# Current_Sense_Board.net
KiCad netlist of a schematic drawn in EAGLE
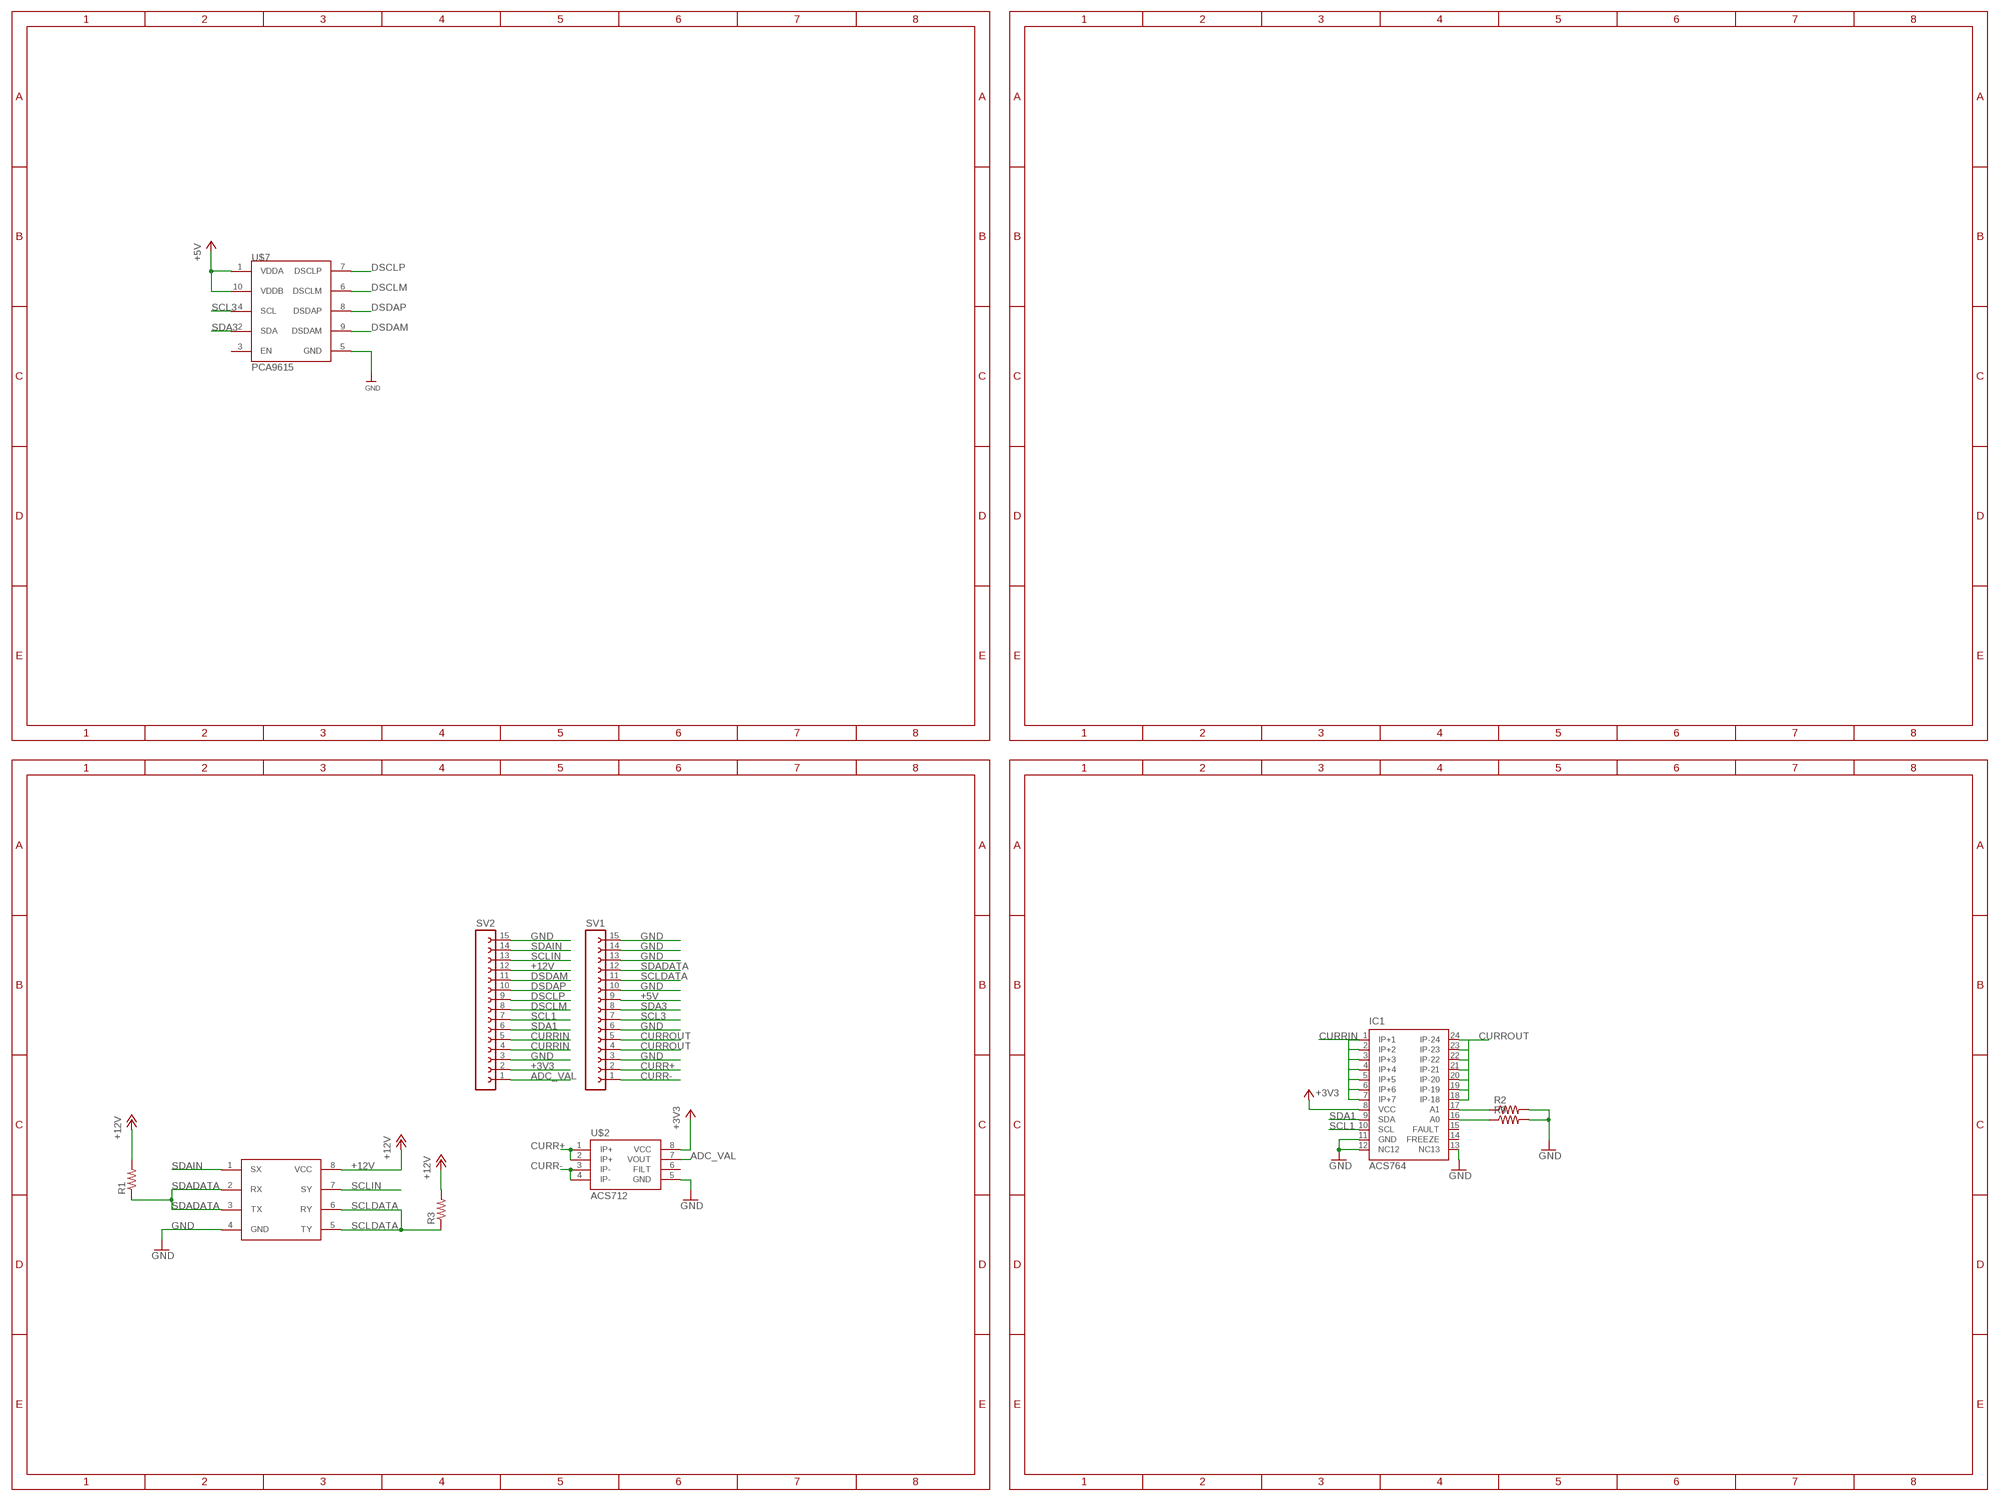
[diagram p0: schematic, sheet 1]

(export (version "E")
  (design (tool "Eeschema 10.0.6"))
  (components
    (comp (ref "IC1")
      (value "ACS764")
      (footprint "eagle-import:SSOP24")
      (libsource (lib "eagle-import") (part "ACS764"))
    )
    (comp (ref "R1")
      (value "RESISTOR0603")
      (footprint "eagle-import:0603-RES")
      (libsource (lib "eagle-import") (part "RESISTOR0603"))
    )
    (comp (ref "R2")
      (value "RESISTOR0603")
      (footprint "eagle-import:0603-RES")
      (libsource (lib "eagle-import") (part "RESISTOR0603"))
    )
    (comp (ref "R3")
      (value "RESISTOR0603")
      (footprint "eagle-import:0603-RES")
      (libsource (lib "eagle-import") (part "RESISTOR0603"))
    )
    (comp (ref "R9")
      (value "RESISTOR0603")
      (footprint "eagle-import:0603-RES")
      (libsource (lib "eagle-import") (part "RESISTOR0603"))
    )
    (comp (ref "SV1")
      (value "FE15-1")
      (footprint "eagle-import:FE15")
      (libsource (lib "eagle-import") (part "FE15-1"))
    )
    (comp (ref "SV2")
      (value "FE15-1")
      (footprint "eagle-import:FE15")
      (libsource (lib "eagle-import") (part "FE15-1"))
    )
    (comp (ref "U$1")
      (value "PCA9000")
      (footprint "eagle-import:TSSOP8")
      (libsource (lib "eagle-import") (part "PCA9000"))
    )
    (comp (ref "U$2")
      (value "ACS712")
      (footprint "eagle-import:SO08")
      (libsource (lib "eagle-import") (part "ACS712"))
    )
    (comp (ref "U$7")
      (value "PCA9615")
      (footprint "eagle-import:MSOP_10")
      (libsource (lib "eagle-import") (part "PCA9615"))
    )
  )
  (nets
    (net (code "1") (name "+3V3") (class "Default")
      (node (ref "IC1") (pin "8") (pinfunction "VCC_8") (pintype "bidirectional"))
      (node (ref "SV2") (pin "2") (pinfunction "2_2") (pintype "passive"))
      (node (ref "U$2") (pin "8") (pinfunction "VCC_8") (pintype "bidirectional"))
    )
    (net (code "2") (name "+5V") (class "Default")
      (node (ref "SV1") (pin "9") (pinfunction "9_9") (pintype "passive"))
      (node (ref "U$7") (pin "1") (pinfunction "VDDA_1") (pintype "bidirectional"))
      (node (ref "U$7") (pin "10") (pinfunction "VDDB_10") (pintype "bidirectional"))
    )
    (net (code "3") (name "+12V") (class "Default")
      (node (ref "R1") (pin "2") (pinfunction "2_2") (pintype "passive"))
      (node (ref "R3") (pin "2") (pinfunction "2_2") (pintype "passive"))
      (node (ref "SV2") (pin "12") (pinfunction "12_12") (pintype "passive"))
      (node (ref "U$1") (pin "8") (pinfunction "VCC_8") (pintype "bidirectional"))
    )
    (net (code "4") (name "ADC_VAL") (class "Default")
      (node (ref "SV2") (pin "1") (pinfunction "1_1") (pintype "passive"))
      (node (ref "U$2") (pin "7") (pinfunction "VOUT_7") (pintype "bidirectional"))
    )
    (net (code "5") (name "CURR+") (class "Default")
      (node (ref "SV1") (pin "2") (pinfunction "2_2") (pintype "passive"))
      (node (ref "U$2") (pin "1") (pinfunction "IP+_1") (pintype "bidirectional"))
      (node (ref "U$2") (pin "2") (pinfunction "IP+_2") (pintype "bidirectional"))
    )
    (net (code "6") (name "CURR-") (class "Default")
      (node (ref "SV1") (pin "1") (pinfunction "1_1") (pintype "passive"))
      (node (ref "U$2") (pin "3") (pinfunction "IP-_3") (pintype "bidirectional"))
      (node (ref "U$2") (pin "4") (pinfunction "IP-_4") (pintype "bidirectional"))
    )
    (net (code "7") (name "CURRIN") (class "Default")
      (node (ref "IC1") (pin "1") (pinfunction "IP+1_1") (pintype "bidirectional"))
      (node (ref "IC1") (pin "2") (pinfunction "IP+2_2") (pintype "bidirectional"))
      (node (ref "IC1") (pin "3") (pinfunction "IP+3_3") (pintype "bidirectional"))
      (node (ref "IC1") (pin "4") (pinfunction "IP+4_4") (pintype "bidirectional"))
      (node (ref "IC1") (pin "5") (pinfunction "IP+5_5") (pintype "bidirectional"))
      (node (ref "IC1") (pin "6") (pinfunction "IP+6_6") (pintype "bidirectional"))
      (node (ref "IC1") (pin "7") (pinfunction "IP+7_7") (pintype "bidirectional"))
      (node (ref "SV2") (pin "4") (pinfunction "4_4") (pintype "passive"))
      (node (ref "SV2") (pin "5") (pinfunction "5_5") (pintype "passive"))
    )
    (net (code "8") (name "CURROUT") (class "Default")
      (node (ref "IC1") (pin "18") (pinfunction "IP-18_18") (pintype "bidirectional"))
      (node (ref "IC1") (pin "19") (pinfunction "IP-19_19") (pintype "bidirectional"))
      (node (ref "IC1") (pin "20") (pinfunction "IP-20_20") (pintype "bidirectional"))
      (node (ref "IC1") (pin "21") (pinfunction "IP-21_21") (pintype "bidirectional"))
      (node (ref "IC1") (pin "22") (pinfunction "IP-22_22") (pintype "bidirectional"))
      (node (ref "IC1") (pin "23") (pinfunction "IP-23_23") (pintype "bidirectional"))
      (node (ref "IC1") (pin "24") (pinfunction "IP-24_24") (pintype "bidirectional"))
      (node (ref "SV1") (pin "4") (pinfunction "4_4") (pintype "passive"))
      (node (ref "SV1") (pin "5") (pinfunction "5_5") (pintype "passive"))
    )
    (net (code "9") (name "DSCLM") (class "Default")
      (node (ref "SV2") (pin "8") (pinfunction "8_8") (pintype "passive"))
      (node (ref "U$7") (pin "6") (pinfunction "DSCLM_6") (pintype "bidirectional"))
    )
    (net (code "10") (name "DSCLP") (class "Default")
      (node (ref "SV2") (pin "9") (pinfunction "9_9") (pintype "passive"))
      (node (ref "U$7") (pin "7") (pinfunction "DSCLP_7") (pintype "bidirectional"))
    )
    (net (code "11") (name "DSDAM") (class "Default")
      (node (ref "SV2") (pin "11") (pinfunction "11_11") (pintype "passive"))
      (node (ref "U$7") (pin "9") (pinfunction "DSDAM_9") (pintype "bidirectional"))
    )
    (net (code "12") (name "DSDAP") (class "Default")
      (node (ref "SV2") (pin "10") (pinfunction "10_10") (pintype "passive"))
      (node (ref "U$7") (pin "8") (pinfunction "DSDAP_8") (pintype "bidirectional"))
    )
    (net (code "13") (name "GND") (class "Default")
      (node (ref "IC1") (pin "11") (pinfunction "GND_11") (pintype "bidirectional"))
      (node (ref "IC1") (pin "12") (pinfunction "NC12_12") (pintype "bidirectional"))
      (node (ref "IC1") (pin "13") (pinfunction "NC13_13") (pintype "bidirectional"))
      (node (ref "R2") (pin "2") (pinfunction "2_2") (pintype "passive"))
      (node (ref "R9") (pin "2") (pinfunction "2_2") (pintype "passive"))
      (node (ref "SV1") (pin "10") (pinfunction "10_10") (pintype "passive"))
      (node (ref "SV1") (pin "13") (pinfunction "13_13") (pintype "passive"))
      (node (ref "SV1") (pin "14") (pinfunction "14_14") (pintype "passive"))
      (node (ref "SV1") (pin "15") (pinfunction "15_15") (pintype "passive"))
      (node (ref "SV1") (pin "3") (pinfunction "3_3") (pintype "passive"))
      (node (ref "SV1") (pin "6") (pinfunction "6_6") (pintype "passive"))
      (node (ref "SV2") (pin "15") (pinfunction "15_15") (pintype "passive"))
      (node (ref "SV2") (pin "3") (pinfunction "3_3") (pintype "passive"))
      (node (ref "U$1") (pin "4") (pinfunction "GND_4") (pintype "bidirectional"))
      (node (ref "U$2") (pin "5") (pinfunction "GND_5") (pintype "bidirectional"))
      (node (ref "U$7") (pin "5") (pinfunction "GND_5") (pintype "bidirectional"))
    )
    (net (code "14") (name "Net-(IC1-A0)") (class "Default")
      (node (ref "IC1") (pin "16") (pinfunction "A0_16") (pintype "bidirectional"))
      (node (ref "R9") (pin "1") (pinfunction "1_1") (pintype "passive"))
    )
    (net (code "15") (name "Net-(IC1-A1)") (class "Default")
      (node (ref "IC1") (pin "17") (pinfunction "A1_17") (pintype "bidirectional"))
      (node (ref "R2") (pin "1") (pinfunction "1_1") (pintype "passive"))
    )
    (net (code "16") (name "SCL1") (class "Default")
      (node (ref "IC1") (pin "10") (pinfunction "SCL_10") (pintype "bidirectional"))
      (node (ref "SV2") (pin "7") (pinfunction "7_7") (pintype "passive"))
    )
    (net (code "17") (name "SCL3") (class "Default")
      (node (ref "SV1") (pin "7") (pinfunction "7_7") (pintype "passive"))
      (node (ref "U$7") (pin "4") (pinfunction "SCL_4") (pintype "bidirectional"))
    )
    (net (code "18") (name "SCLDATA") (class "Default")
      (node (ref "R3") (pin "1") (pinfunction "1_1") (pintype "passive"))
      (node (ref "SV1") (pin "11") (pinfunction "11_11") (pintype "passive"))
      (node (ref "U$1") (pin "5") (pinfunction "TY_5") (pintype "bidirectional"))
      (node (ref "U$1") (pin "6") (pinfunction "RY_6") (pintype "bidirectional"))
    )
    (net (code "19") (name "SCLIN") (class "Default")
      (node (ref "SV2") (pin "13") (pinfunction "13_13") (pintype "passive"))
      (node (ref "U$1") (pin "7") (pinfunction "SY_7") (pintype "bidirectional"))
    )
    (net (code "20") (name "SDA1") (class "Default")
      (node (ref "IC1") (pin "9") (pinfunction "SDA_9") (pintype "bidirectional"))
      (node (ref "SV2") (pin "6") (pinfunction "6_6") (pintype "passive"))
    )
    (net (code "21") (name "SDA3") (class "Default")
      (node (ref "SV1") (pin "8") (pinfunction "8_8") (pintype "passive"))
      (node (ref "U$7") (pin "2") (pinfunction "SDA_2") (pintype "bidirectional"))
    )
    (net (code "22") (name "SDADATA") (class "Default")
      (node (ref "R1") (pin "1") (pinfunction "1_1") (pintype "passive"))
      (node (ref "SV1") (pin "12") (pinfunction "12_12") (pintype "passive"))
      (node (ref "U$1") (pin "2") (pinfunction "RX_2") (pintype "bidirectional"))
      (node (ref "U$1") (pin "3") (pinfunction "TX_3") (pintype "bidirectional"))
    )
    (net (code "23") (name "SDAIN") (class "Default")
      (node (ref "SV2") (pin "14") (pinfunction "14_14") (pintype "passive"))
      (node (ref "U$1") (pin "1") (pinfunction "SX_1") (pintype "bidirectional"))
    )
    (net (code "24") (name "unconnected-(IC1-FAULT-Pad15)") (class "Default")
      (node (ref "IC1") (pin "15") (pinfunction "FAULT_15") (pintype "bidirectional"))
    )
    (net (code "25") (name "unconnected-(IC1-FREEZE-Pad14)") (class "Default")
      (node (ref "IC1") (pin "14") (pinfunction "FREEZE_14") (pintype "bidirectional"))
    )
    (net (code "26") (name "unconnected-(U$2-FILT-Pad6)") (class "Default")
      (node (ref "U$2") (pin "6") (pinfunction "FILT_6") (pintype "bidirectional"))
    )
    (net (code "27") (name "unconnected-(U$7-EN-Pad3)") (class "Default")
      (node (ref "U$7") (pin "3") (pinfunction "EN_3") (pintype "bidirectional"))
    )
  )
)
